# Wattuino-Tiny85_v10.net
KiCad netlist of a schematic drawn in EAGLE
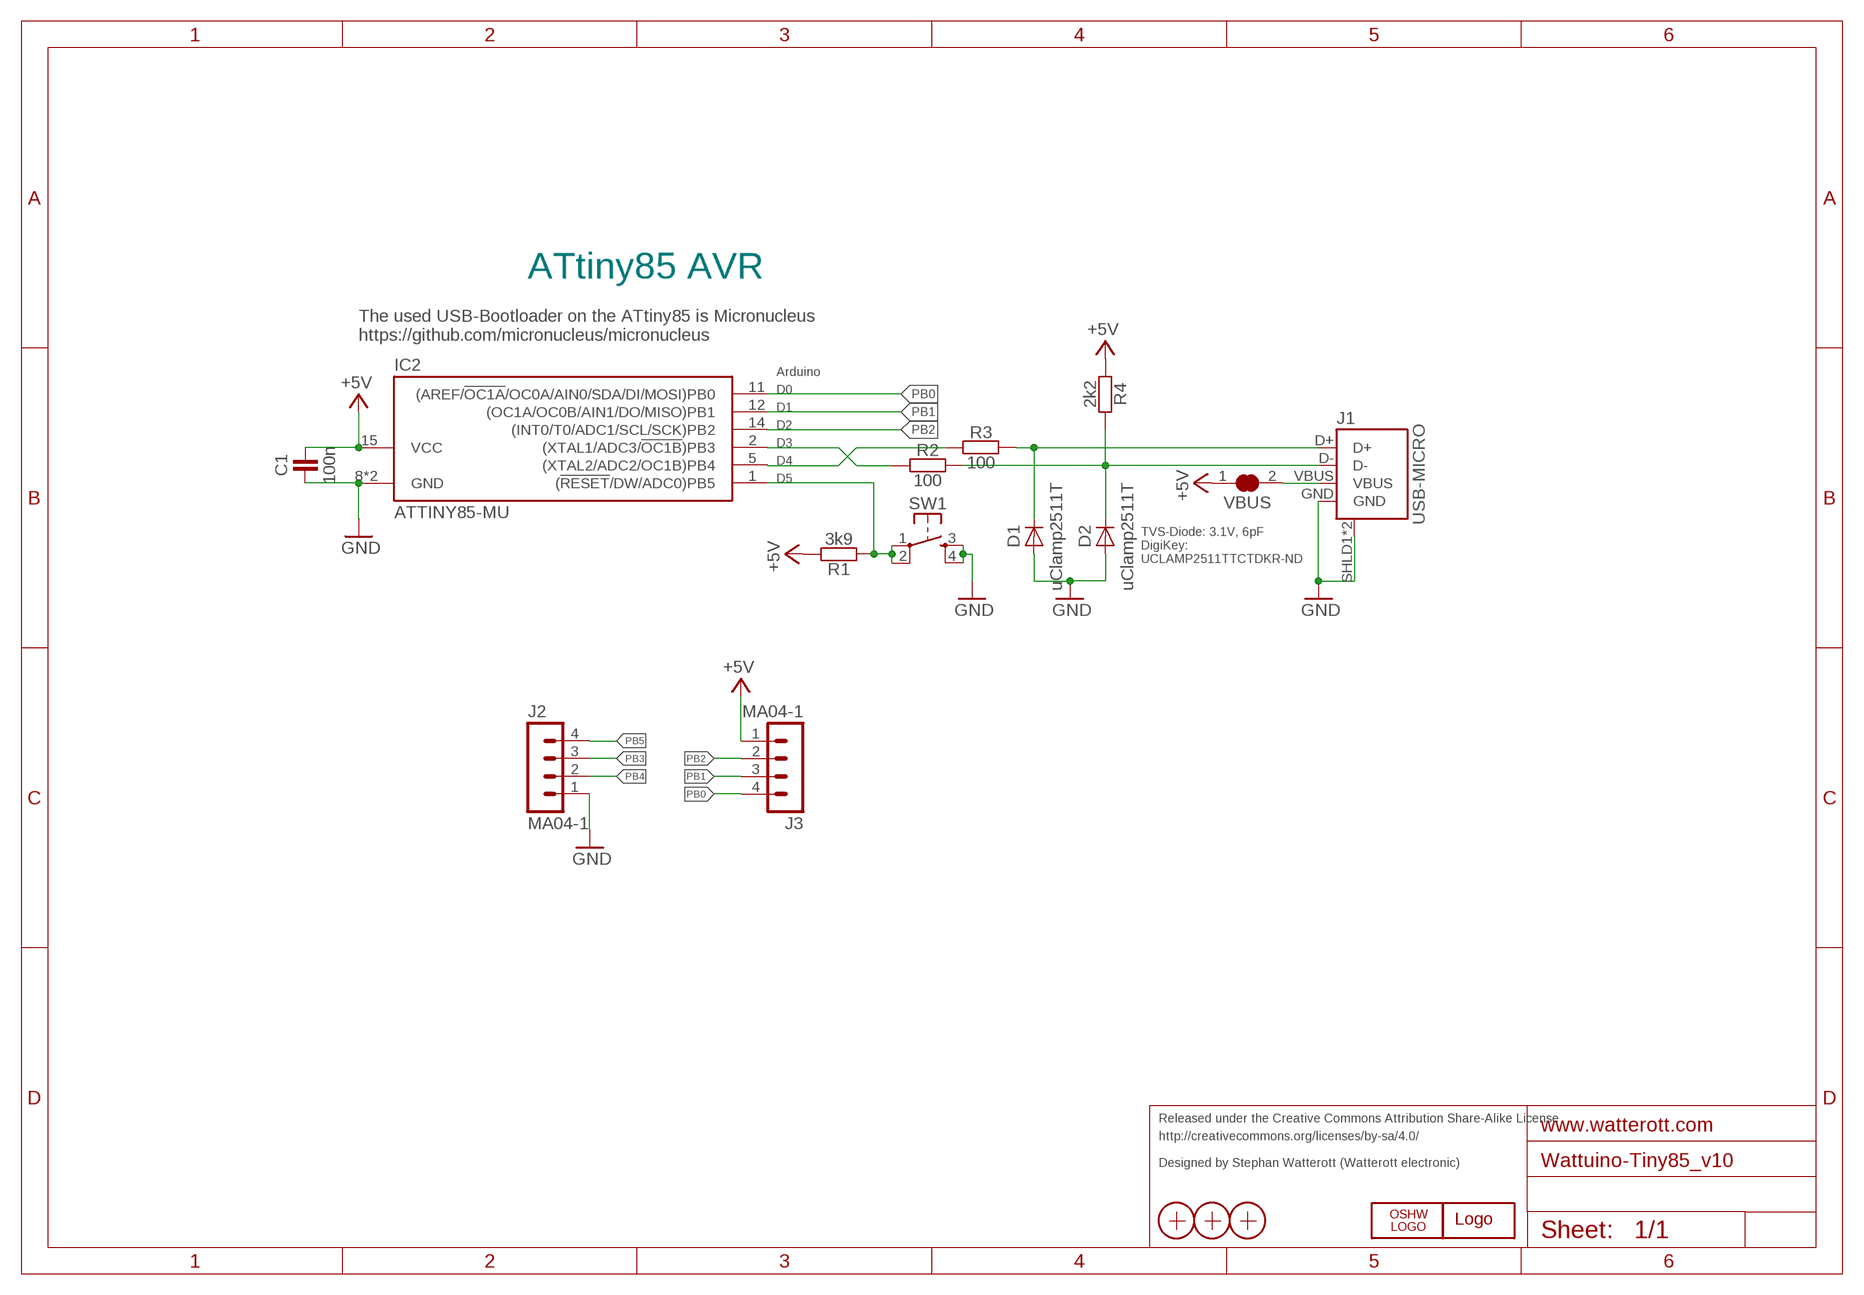
[diagram p0: schematic, sheet 1]

(export (version "E")
  (design (tool "Eeschema 10.0.6"))
  (components
    (comp (ref "C1")
      (value "100n")
      (footprint "eagle-import:R0402")
      (libsource (lib "eagle-import") (part "CAPACITOR-C0402"))
    )
    (comp (ref "D1")
      (value "uClamp2511T")
      (footprint "eagle-import:SOD882")
      (libsource (lib "eagle-import") (part "DIODE-SOD882"))
    )
    (comp (ref "D2")
      (value "uClamp2511T")
      (footprint "eagle-import:SOD882")
      (libsource (lib "eagle-import") (part "DIODE-SOD882"))
    )
    (comp (ref "IC2")
      (value "ATTINY85-MU")
      (footprint "eagle-import:QFN20-PAD")
      (libsource (lib "eagle-import") (part "ATTINY85-MU"))
    )
    (comp (ref "J1")
      (value "USB-MICRO")
      (footprint "eagle-import:USB-MICRO-10103594")
      (libsource (lib "eagle-import") (part "USB-MICRO"))
    )
    (comp (ref "J2")
      (value "MA04-1")
      (footprint "eagle-import:MA04-1")
      (libsource (lib "eagle-import") (part "MA04-1"))
    )
    (comp (ref "J3")
      (value "MA04-1")
      (footprint "eagle-import:MA04-1")
      (libsource (lib "eagle-import") (part "MA04-1"))
    )
    (comp (ref "LOGO1")
      (value "LOGO-S_PLACE_S")
      (footprint "eagle-import:SPARK_TPLACE_S")
      (libsource (lib "eagle-import") (part "LOGO-S_PLACE_S"))
    )
    (comp (ref "LOGO2")
      (value "OSHW_LOGOX0070")
      (footprint "eagle-import:OSHW_6X70")
      (libsource (lib "eagle-import") (part "OSHW_LOGOX0070"))
    )
    (comp (ref "R1")
      (value "3k9")
      (footprint "eagle-import:R0402")
      (libsource (lib "eagle-import") (part "RESISTOR-R0402"))
    )
    (comp (ref "R2")
      (value "100")
      (footprint "eagle-import:R0402")
      (libsource (lib "eagle-import") (part "RESISTOR-R0402"))
    )
    (comp (ref "R3")
      (value "100")
      (footprint "eagle-import:R0402")
      (libsource (lib "eagle-import") (part "RESISTOR-R0402"))
    )
    (comp (ref "R4")
      (value "2k2")
      (footprint "eagle-import:R0402")
      (libsource (lib "eagle-import") (part "RESISTOR-R0402"))
    )
    (comp (ref "SW1")
      (value "SW-TACTILE-PTS840P")
      (footprint "eagle-import:SW_PTS840P")
      (libsource (lib "eagle-import") (part "SW-TACTILE-PTS840P"))
    )
    (comp (ref "VBUS")
      (value "JUMPER2-0603-NC")
      (footprint "eagle-import:JUMPER2-0603_NC")
      (libsource (lib "eagle-import") (part "JUMPER2-0603-NC"))
    )
    (comp (ref "X1")
      (value "PASSER-07")
      (footprint "eagle-import:PASSER_07MM")
      (libsource (lib "eagle-import") (part "PASSER-07"))
    )
    (comp (ref "X2")
      (value "PASSER-07")
      (footprint "eagle-import:PASSER_07MM")
      (libsource (lib "eagle-import") (part "PASSER-07"))
    )
    (comp (ref "X3")
      (value "PASSER-07")
      (footprint "eagle-import:PASSER_07MM")
      (libsource (lib "eagle-import") (part "PASSER-07"))
    )
  )
  (nets
    (net (code "1") (name "+5V") (class "Default")
      (node (ref "C1") (pin "2") (pinfunction "2_2") (pintype "passive"))
      (node (ref "IC2") (pin "15") (pinfunction "VCC_15") (pintype "power_in"))
      (node (ref "J3") (pin "1") (pinfunction "1_1") (pintype "passive"))
      (node (ref "R1") (pin "2") (pinfunction "2_2") (pintype "passive"))
      (node (ref "R4") (pin "1") (pinfunction "1_1") (pintype "passive"))
      (node (ref "VBUS") (pin "1") (pinfunction "1_1") (pintype "passive"))
    )
    (net (code "2") (name "GND") (class "Default")
      (node (ref "C1") (pin "1") (pinfunction "1_1") (pintype "passive"))
      (node (ref "D1") (pin "A") (pinfunction "A_A") (pintype "passive"))
      (node (ref "D2") (pin "A") (pinfunction "A_A") (pintype "passive"))
      (node (ref "IC2") (pin "8") (pinfunction "GND_8") (pintype "power_in"))
      (node (ref "IC2") (pin "TP") (pinfunction "GND_TP") (pintype "power_in"))
      (node (ref "J1") (pin "GND") (pinfunction "GND_GND") (pintype "power_in"))
      (node (ref "J1") (pin "SHLD1") (pinfunction "SHIELD_SHLD1") (pintype "passive"))
      (node (ref "J1") (pin "SHLD2") (pinfunction "SHIELD_SHLD2") (pintype "passive"))
      (node (ref "J2") (pin "1") (pinfunction "1_1") (pintype "passive"))
      (node (ref "SW1") (pin "3") (pinfunction "S1_3") (pintype "passive"))
      (node (ref "SW1") (pin "4") (pinfunction "S2_4") (pintype "passive"))
    )
    (net (code "3") (name "Net-(D1-PadC)") (class "Default")
      (node (ref "D1") (pin "C") (pinfunction "C_C") (pintype "passive"))
      (node (ref "J1") (pin "D+") (pinfunction "D+_D+") (pintype "bidirectional"))
      (node (ref "R3") (pin "2") (pinfunction "2_2") (pintype "passive"))
    )
    (net (code "4") (name "Net-(D2-PadC)") (class "Default")
      (node (ref "D2") (pin "C") (pinfunction "C_C") (pintype "passive"))
      (node (ref "J1") (pin "D-") (pinfunction "D-_D-") (pintype "bidirectional"))
      (node (ref "R2") (pin "2") (pinfunction "2_2") (pintype "passive"))
      (node (ref "R4") (pin "2") (pinfunction "2_2") (pintype "passive"))
    )
    (net (code "5") (name "Net-(J1-PadVBUS)") (class "Default")
      (node (ref "J1") (pin "VBUS") (pinfunction "VBUS_VBUS") (pintype "power_in"))
      (node (ref "VBUS") (pin "2") (pinfunction "2_2") (pintype "passive"))
    )
    (net (code "6") (name "PB0") (class "Default")
      (node (ref "IC2") (pin "11") (pinfunction "(AREF/~{OC1A}/OC0A/AIN0/SDA/DI/MOSI)PB0_11") (pintype "bidirectional"))
      (node (ref "J3") (pin "4") (pinfunction "4_4") (pintype "passive"))
    )
    (net (code "7") (name "PB1") (class "Default")
      (node (ref "IC2") (pin "12") (pinfunction "(OC1A/OC0B/AIN1/DO/MISO)PB1_12") (pintype "bidirectional"))
      (node (ref "J3") (pin "3") (pinfunction "3_3") (pintype "passive"))
    )
    (net (code "8") (name "PB2") (class "Default")
      (node (ref "IC2") (pin "14") (pinfunction "(INT0/T0/ADC1/SCL/SCK)PB2_14") (pintype "bidirectional"))
      (node (ref "J3") (pin "2") (pinfunction "2_2") (pintype "passive"))
    )
    (net (code "9") (name "PB3") (class "Default")
      (node (ref "IC2") (pin "2") (pinfunction "(XTAL1/ADC3/~{OC1B})PB3_2") (pintype "bidirectional"))
      (node (ref "J2") (pin "3") (pinfunction "3_3") (pintype "passive"))
      (node (ref "R2") (pin "1") (pinfunction "1_1") (pintype "passive"))
    )
    (net (code "10") (name "PB4") (class "Default")
      (node (ref "IC2") (pin "5") (pinfunction "(XTAL2/ADC2/OC1B)PB4_5") (pintype "bidirectional"))
      (node (ref "J2") (pin "2") (pinfunction "2_2") (pintype "passive"))
      (node (ref "R3") (pin "1") (pinfunction "1_1") (pintype "passive"))
    )
    (net (code "11") (name "PB5") (class "Default")
      (node (ref "IC2") (pin "1") (pinfunction "(~{RESET}/DW/ADC0)PB5_1") (pintype "bidirectional"))
      (node (ref "J2") (pin "4") (pinfunction "4_4") (pintype "passive"))
      (node (ref "R1") (pin "1") (pinfunction "1_1") (pintype "passive"))
      (node (ref "SW1") (pin "1") (pinfunction "P1_1") (pintype "passive"))
      (node (ref "SW1") (pin "2") (pinfunction "P2_2") (pintype "passive"))
    )
  )
)
